# SH7_-_BROADCOM_ENCODER.net
KiCad netlist of a schematic drawn in Altium Designer
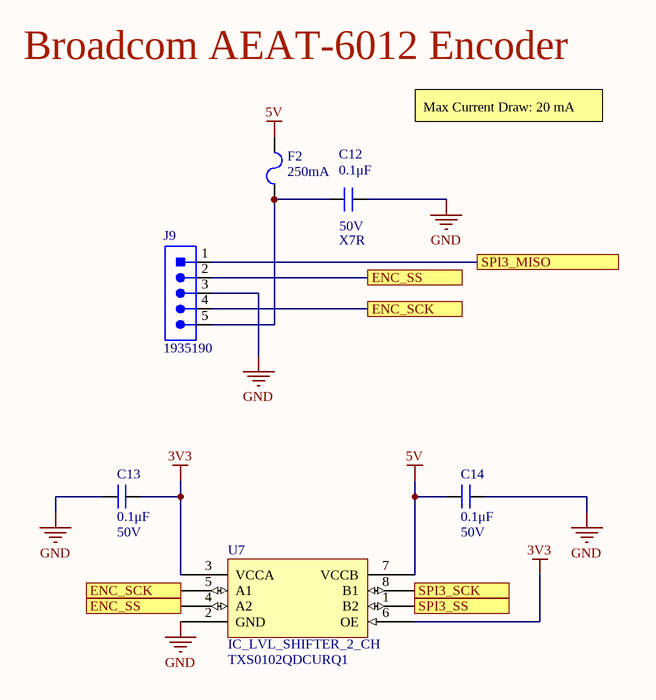
[diagram p0: SH7 - BROADCOM ENCODER.SchDoc]

(export (version "E")
  (design (tool "Eeschema 10.0.6"))
  (components
    (comp (ref "C12")
      (value "0.1μF")
      (footprint "CAP0603")
      (description "CAP CER 0.1UF 50V X7R 0603")
      (fields
        (field (name "DIELECTRIC") "X7R")
        (field (name "VOLTAGE RATING") "50V")
        (field (name "Comment") "CAP_0.1uF_50V_0603")
      )
      (libsource (lib "UWRT_Schematic_Library_2020") (part "CAP_0.1uF_50V_0603"))
    )
    (comp (ref "C13")
      (value "0.1μF")
      (footprint "CAP2012")
      (description "CAP CER 0.1UF 50V X7R 0805")
      (fields
        (field (name "LCSC PART #") "C49678")
        (field (name "VOLTAGE RATING") "50V")
        (field (name "Comment") "CAP_0.1uF_50V_0805")
      )
      (libsource (lib "UWRT_Schematic_Library_2020") (part "CAP_0.1uF_50V_0805"))
    )
    (comp (ref "C14")
      (value "0.1μF")
      (footprint "CAP2012")
      (description "CAP CER 0.1UF 50V X7R 0805")
      (fields
        (field (name "LCSC PART #") "C49678")
        (field (name "VOLTAGE RATING") "50V")
        (field (name "Comment") "CAP_0.1uF_50V_0805")
      )
      (libsource (lib "UWRT_Schematic_Library_2020") (part "CAP_0.1uF_50V_0805"))
    )
    (comp (ref "F2")
      (value "FUSE_250mA_0603")
      (footprint "FUSE_0603")
      (description "FUSE SMD 250mA 32V")
      (fields (field (name "CURRENT RATING") "250mA"))
      (libsource (lib "UWRT_Schematic_Library_2020") (part "FUSE_250mA_0603"))
    )
    (comp (ref "J9")
      (value "CON_5POS_SCREW_TERM")
      (footprint "1935190")
      (description "TERM BLK 5POS SIDE ENTRY 5MM")
      (fields (field (name "MANUFACTURER PART NUMBER 1") "1935190"))
      (libsource (lib "UWRT_Schematic_Library_2020") (part "CON_5POS_SCREW_TERM"))
    )
    (comp (ref "U7")
      (value "IC_LVL_SHIFTER_2_CH")
      (footprint "TXS0102QDCURQ1")
      (description "IC TRNSLTR BIDIRECTIONAL US8")
      (fields (field (name "MANUFACTURER PART NUMBER 1") "TXS0102QDCURQ1"))
      (libsource (lib "UWRT_Schematic_Library_2020") (part "IC_LVL_SHIFTER_2_CH"))
    )
  )
  (nets
    (net (code "1") (name "/ENC_SCK") (class "Default")
      (node (ref "J9") (pin "4") (pinfunction "4_4") (pintype "passive"))
      (node (ref "U7") (pin "5") (pinfunction "A1_5") (pintype "bidirectional"))
    )
    (net (code "2") (name "/ENC_SS") (class "Default")
      (node (ref "J9") (pin "2") (pinfunction "2_2") (pintype "passive"))
      (node (ref "U7") (pin "4") (pinfunction "A2_4") (pintype "bidirectional"))
    )
    (net (code "3") (name "/SPI3_MISO") (class "Default")
      (node (ref "J9") (pin "1") (pinfunction "1_1") (pintype "passive"))
    )
    (net (code "4") (name "/SPI3_SCK") (class "Default")
      (node (ref "U7") (pin "8") (pinfunction "B1_8") (pintype "bidirectional"))
    )
    (net (code "5") (name "/SPI3_SS") (class "Default")
      (node (ref "U7") (pin "1") (pinfunction "B2_1") (pintype "bidirectional"))
    )
    (net (code "6") (name "3V3") (class "Default")
      (node (ref "C13") (pin "2") (pinfunction "2_2") (pintype "passive"))
      (node (ref "U7") (pin "3") (pinfunction "VCCA_3") (pintype "power_in"))
      (node (ref "U7") (pin "6") (pinfunction "OE_6") (pintype "input"))
    )
    (net (code "7") (name "5V") (class "Default")
      (node (ref "C14") (pin "1") (pinfunction "1_1") (pintype "passive"))
      (node (ref "F2") (pin "2") (pinfunction "2_2") (pintype "passive"))
      (node (ref "U7") (pin "7") (pinfunction "VCCB_7") (pintype "power_in"))
    )
    (net (code "8") (name "GND") (class "Default")
      (node (ref "C12") (pin "1") (pinfunction "1_1") (pintype "passive"))
      (node (ref "C13") (pin "1") (pinfunction "1_1") (pintype "passive"))
      (node (ref "C14") (pin "2") (pinfunction "2_2") (pintype "passive"))
      (node (ref "J9") (pin "3") (pinfunction "3_3") (pintype "passive"))
      (node (ref "U7") (pin "2") (pinfunction "GND_2") (pintype "power_in"))
    )
    (net (code "9") (name "Net-(C12-Pad2)") (class "Default")
      (node (ref "C12") (pin "2") (pinfunction "2_2") (pintype "passive"))
      (node (ref "F2") (pin "1") (pinfunction "1_1") (pintype "passive"))
      (node (ref "J9") (pin "5") (pinfunction "5_5") (pintype "passive"))
    )
  )
)
